# discharge-tsmp.net
KiCad netlist of a schematic drawn in Altium Designer
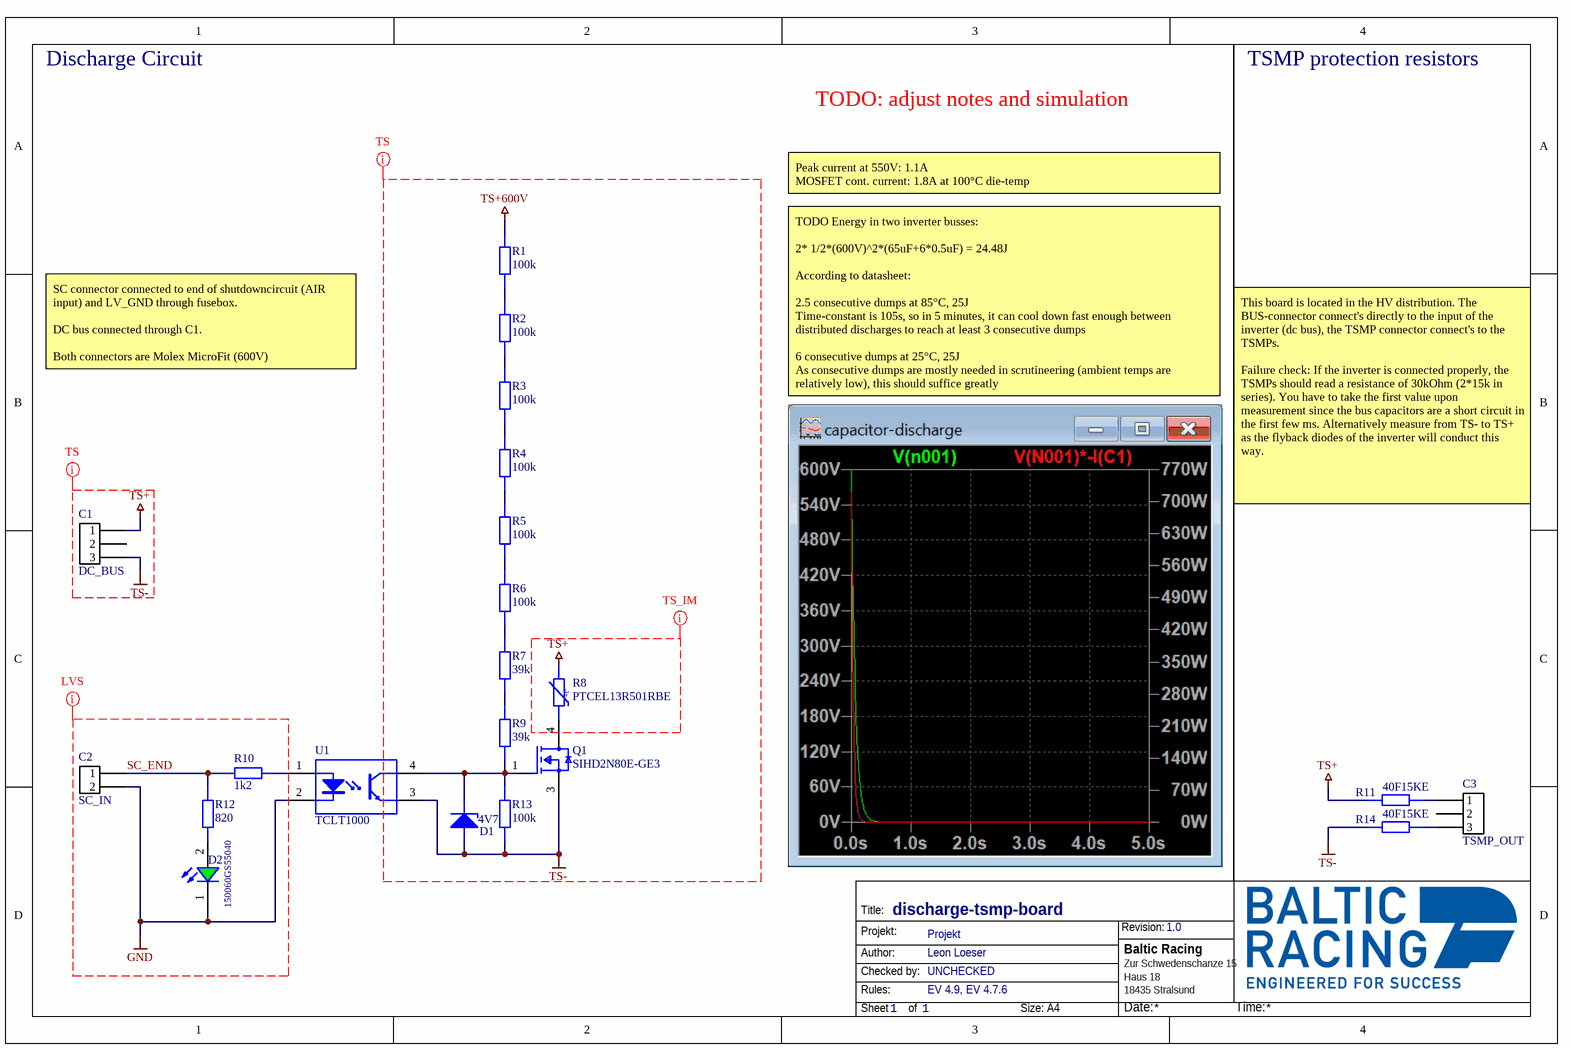
[diagram p0: discharge-tsmp.SchDoc]

(export (version "E")
  (design (tool "Eeschema 10.0.6"))
  (components
    (comp (ref "C1")
      (value "DC_BUS")
      (footprint "43650-0309")
      (description "Molex Micro-Fit 3.0 3-Pin\r\n600V\r\n8.5A")
      (libsource (lib "Standardbauteile") (part "MicroFit3.0 3-Pin"))
    )
    (comp (ref "C2")
      (value "SC_IN")
      (footprint "43650-0200")
      (description "Molex Micro-Fit 3.0 2-Pin\r\n600V\r\n8.5A")
      (libsource (lib "Standardbauteile") (part "MicroFit3.0 2-Pin"))
    )
    (comp (ref "C3")
      (value "TSMP_OUT")
      (footprint "43650-0309")
      (description "Molex Micro-Fit 3.0 3-Pin\r\n600V\r\n8.5A")
      (libsource (lib "Standardbauteile") (part "MicroFit3.0 3-Pin"))
    )
    (comp (ref "D1")
      (value "4V7")
      (footprint "SOT23")
      (libsource (lib "Standardbauteile") (part "SMD Zener Diode"))
    )
    (comp (ref "D2")
      (value "150060GS55040")
      (footprint "WL-SMCW_0603_H=0.7")
      (description "SMT Mono-color Chip LED Waterclear WL-SMCW, size 0603, Green, 3.2 V, 140 deg, 430 mcd")
      (fields (field (name "PART NUMBER") "150060GS75000") (field (name "PUBLISHER") "Wurth Elektronik"))
      (libsource (lib "ALTIUM-WL-SMCW-rev18c") (part "150060GS75000"))
    )
    (comp (ref "Q1")
      (value "SIHD2N80E-GE3")
      (footprint "FP-T16-0236-MFG")
      (description "N-Channel 800V 2.8A (Tc) 62.5W (Tc) Surface Mount D-PAK (TO-252AA)")
      (fields (field (name "MANUFACTURER") "Vishay"))
      (libsource (lib "Altium Content Vault") (part "86656c45bbbddc162aead764a772c09"))
    )
    (comp (ref "R1")
      (value "100k")
      (footprint "STACKPOLE CSR1206")
      (description "Resistor with multiple footprints")
      (fields (field (name "Comment") "SMD Resistor"))
      (libsource (lib "Standardbauteile") (part "SMD Resistor"))
    )
    (comp (ref "R2")
      (value "100k")
      (footprint "STACKPOLE CSR1206")
      (description "Resistor with multiple footprints")
      (fields (field (name "Comment") "SMD Resistor"))
      (libsource (lib "Standardbauteile") (part "SMD Resistor"))
    )
    (comp (ref "R3")
      (value "100k")
      (footprint "STACKPOLE CSR1206")
      (description "Resistor with multiple footprints")
      (fields (field (name "Comment") "SMD Resistor"))
      (libsource (lib "Standardbauteile") (part "SMD Resistor"))
    )
    (comp (ref "R4")
      (value "100k")
      (footprint "STACKPOLE CSR1206")
      (description "Resistor with multiple footprints")
      (fields (field (name "Comment") "SMD Resistor"))
      (libsource (lib "Standardbauteile") (part "SMD Resistor"))
    )
    (comp (ref "R5")
      (value "100k")
      (footprint "STACKPOLE CSR1206")
      (description "Resistor with multiple footprints")
      (fields (field (name "Comment") "SMD Resistor"))
      (libsource (lib "Standardbauteile") (part "SMD Resistor"))
    )
    (comp (ref "R6")
      (value "100k")
      (footprint "STACKPOLE CSR1206")
      (description "Resistor with multiple footprints")
      (fields (field (name "Comment") "SMD Resistor"))
      (libsource (lib "Standardbauteile") (part "SMD Resistor"))
    )
    (comp (ref "R7")
      (value "39k")
      (footprint "STACKPOLE CSR1206")
      (description "Resistor with multiple footprints")
      (fields (field (name "Comment") "SMD Resistor"))
      (libsource (lib "Standardbauteile") (part "SMD Resistor"))
    )
    (comp (ref "R8")
      (value "PTCEL13R501RBE")
      (footprint "PTCEL13_H")
      (description "PTC Thermistors, Inrush Current Limiter and Energy Load-Dump\r\n\r\n500Ohm, 150J")
      (fields (field (name "MANUFACTURER") "Vishay"))
      (libsource (lib "Leon") (part "PTCEL13R501RBE"))
    )
    (comp (ref "R9")
      (value "39k")
      (footprint "STACKPOLE CSR1206")
      (description "Resistor with multiple footprints")
      (fields (field (name "Comment") "SMD Resistor"))
      (libsource (lib "Standardbauteile") (part "SMD Resistor"))
    )
    (comp (ref "R10")
      (value "1k2")
      (footprint "STACKPOLE CSR0603")
      (description "Resistor with multiple footprints")
      (fields (field (name "Comment") "SMD Resistor"))
      (libsource (lib "Standardbauteile") (part "SMD Resistor"))
    )
    (comp (ref "R11")
      (value "40F15KE")
      (footprint "OHMITE_40_SERIES")
      (description "Wirewound Resistors 10watt 15K 1% Axial")
      (fields (field (name "MANUFACTURER") "Ohmite") (field (name "TOLERANCE") "1%"))
      (libsource (lib "Leon") (part "40F15KE"))
    )
    (comp (ref "R12")
      (value "820")
      (footprint "STACKPOLE CSR0603")
      (description "Resistor with multiple footprints")
      (fields (field (name "Comment") "SMD Resistor"))
      (libsource (lib "Standardbauteile") (part "SMD Resistor"))
    )
    (comp (ref "R13")
      (value "100k")
      (footprint "STACKPOLE CSR0603")
      (description "Resistor with multiple footprints")
      (fields (field (name "Comment") "SMD Resistor"))
      (libsource (lib "Standardbauteile") (part "SMD Resistor"))
    )
    (comp (ref "R14")
      (value "40F15KE")
      (footprint "OHMITE_40_SERIES")
      (description "Wirewound Resistors 10watt 15K 1% Axial")
      (fields (field (name "MANUFACTURER") "Ohmite") (field (name "TOLERANCE") "1%"))
      (libsource (lib "Leon") (part "40F15KE"))
    )
    (comp (ref "U1")
      (value "TCLT1000")
      (footprint "VISH-SOP4L-4_V")
      (fields (field (name "MANUFACTURER") "Vishay/Semiconductor"))
      (libsource (lib "Altium Content Vault") (part "OPTO-ACEC-4"))
    )
  )
  (nets
    (net (code "1") (name "/SC_END") (class "Default")
      (node (ref "C2") (pin "1") (pinfunction "1_1") (pintype "passive"))
      (node (ref "R10") (pin "2") (pinfunction "2_2") (pintype "passive"))
      (node (ref "R12") (pin "2") (pinfunction "2_2") (pintype "passive"))
    )
    (net (code "2") (name "GND") (class "Default")
      (node (ref "C2") (pin "2") (pinfunction "2_2") (pintype "passive"))
      (node (ref "D2") (pin "1") (pinfunction "K_1") (pintype "passive"))
      (node (ref "U1") (pin "2") (pinfunction "C_2") (pintype "passive"))
    )
    (net (code "3") (name "Net-(C3-Pad1)") (class "Default")
      (node (ref "C3") (pin "1") (pinfunction "1_1") (pintype "passive"))
      (node (ref "R11") (pin "2") (pinfunction "2_2") (pintype "passive"))
    )
    (net (code "4") (name "Net-(C3-Pad3)") (class "Default")
      (node (ref "C3") (pin "3") (pinfunction "3_3") (pintype "passive"))
      (node (ref "R14") (pin "2") (pinfunction "2_2") (pintype "passive"))
    )
    (net (code "5") (name "Net-(D2-A)") (class "Default")
      (node (ref "D2") (pin "2") (pinfunction "A_2") (pintype "passive"))
      (node (ref "R12") (pin "1") (pinfunction "1_1") (pintype "passive"))
    )
    (net (code "6") (name "Net-(Q1-D)") (class "Default")
      (node (ref "Q1") (pin "4") (pinfunction "D_4") (pintype "passive"))
      (node (ref "R8") (pin "2") (pinfunction "2_2") (pintype "passive"))
    )
    (net (code "7") (name "Net-(Q1-G)") (class "Default")
      (node (ref "D1") (pin "C") (pinfunction "C_C") (pintype "passive"))
      (node (ref "Q1") (pin "1") (pinfunction "G_1") (pintype "passive"))
      (node (ref "R13") (pin "2") (pinfunction "2_2") (pintype "passive"))
      (node (ref "R9") (pin "1") (pinfunction "1_1") (pintype "passive"))
      (node (ref "U1") (pin "4") (pinfunction "C_4") (pintype "passive"))
    )
    (net (code "8") (name "Net-(R1-Pad1)") (class "Default")
      (node (ref "R1") (pin "1") (pinfunction "1_1") (pintype "passive"))
      (node (ref "R2") (pin "2") (pinfunction "2_2") (pintype "passive"))
    )
    (net (code "9") (name "Net-(R2-Pad1)") (class "Default")
      (node (ref "R2") (pin "1") (pinfunction "1_1") (pintype "passive"))
      (node (ref "R3") (pin "2") (pinfunction "2_2") (pintype "passive"))
    )
    (net (code "10") (name "Net-(R3-Pad1)") (class "Default")
      (node (ref "R3") (pin "1") (pinfunction "1_1") (pintype "passive"))
      (node (ref "R4") (pin "2") (pinfunction "2_2") (pintype "passive"))
    )
    (net (code "11") (name "Net-(R4-Pad1)") (class "Default")
      (node (ref "R4") (pin "1") (pinfunction "1_1") (pintype "passive"))
      (node (ref "R5") (pin "2") (pinfunction "2_2") (pintype "passive"))
    )
    (net (code "12") (name "Net-(R5-Pad1)") (class "Default")
      (node (ref "R5") (pin "1") (pinfunction "1_1") (pintype "passive"))
      (node (ref "R6") (pin "2") (pinfunction "2_2") (pintype "passive"))
    )
    (net (code "13") (name "Net-(R6-Pad1)") (class "Default")
      (node (ref "R6") (pin "1") (pinfunction "1_1") (pintype "passive"))
      (node (ref "R7") (pin "2") (pinfunction "2_2") (pintype "passive"))
    )
    (net (code "14") (name "Net-(R7-Pad1)") (class "Default")
      (node (ref "R7") (pin "1") (pinfunction "1_1") (pintype "passive"))
      (node (ref "R9") (pin "2") (pinfunction "2_2") (pintype "passive"))
    )
    (net (code "15") (name "Net-(U1-A)") (class "Default")
      (node (ref "R10") (pin "1") (pinfunction "1_1") (pintype "passive"))
      (node (ref "U1") (pin "1") (pinfunction "A_1") (pintype "passive"))
    )
    (net (code "16") (name "TS+") (class "Default")
      (node (ref "C1") (pin "1") (pinfunction "1_1") (pintype "passive"))
      (node (ref "R11") (pin "1") (pinfunction "1_1") (pintype "passive"))
      (node (ref "R8") (pin "1") (pinfunction "1_1") (pintype "passive"))
    )
    (net (code "17") (name "TS+600V") (class "Default")
      (node (ref "R1") (pin "2") (pinfunction "2_2") (pintype "passive"))
    )
    (net (code "18") (name "TS-") (class "Default")
      (node (ref "C1") (pin "3") (pinfunction "3_3") (pintype "passive"))
      (node (ref "D1") (pin "A") (pinfunction "A_A") (pintype "passive"))
      (node (ref "Q1") (pin "3") (pinfunction "S_3") (pintype "passive"))
      (node (ref "R13") (pin "1") (pinfunction "1_1") (pintype "passive"))
      (node (ref "R14") (pin "1") (pinfunction "1_1") (pintype "passive"))
      (node (ref "U1") (pin "3") (pinfunction "E_3") (pintype "passive"))
    )
    (net (code "19") (name "unconnected-(C1-Pad2)") (class "Default")
      (node (ref "C1") (pin "2") (pinfunction "2_2") (pintype "passive"))
    )
    (net (code "20") (name "unconnected-(C3-Pad2)") (class "Default")
      (node (ref "C3") (pin "2") (pinfunction "2_2") (pintype "passive"))
    )
  )
)
